# pcb.net
KiCad netlist of a schematic drawn in EAGLE
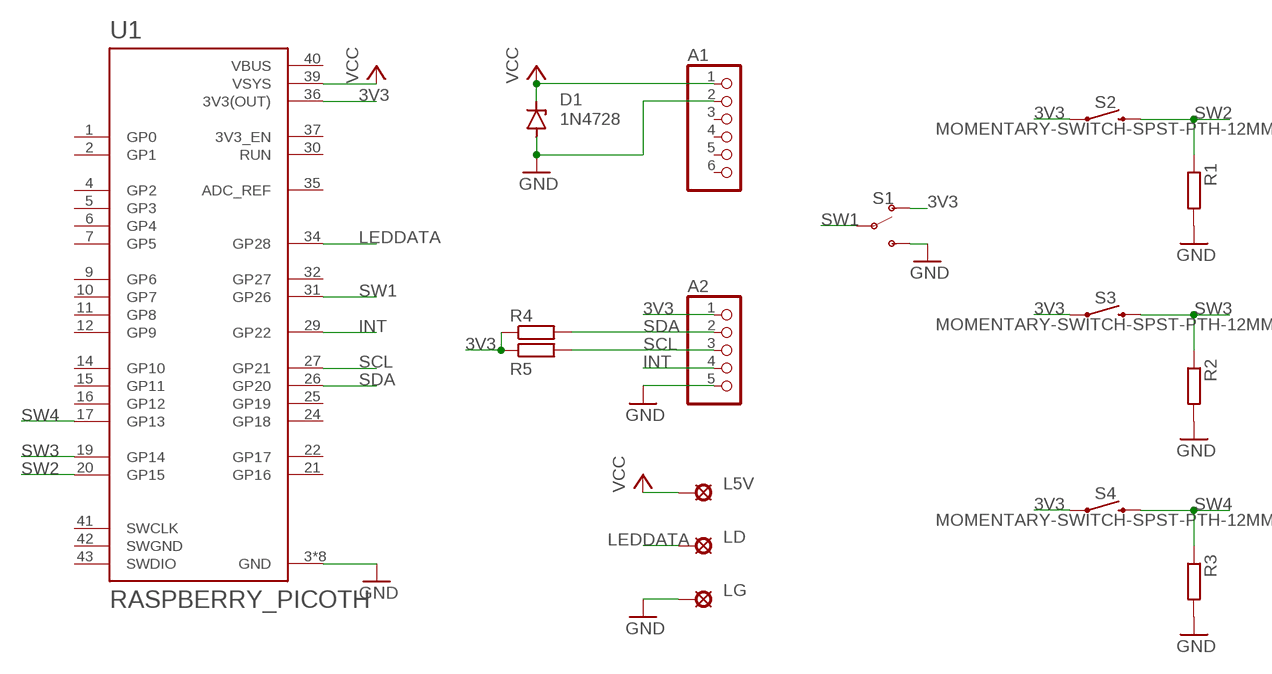
[diagram p0: schematic, sheet 1]

(export (version "E")
  (design (tool "Eeschema 10.0.6"))
  (components
    (comp (ref "A1")
      (value "PINHD-1X6")
      (footprint "eagle-import:1X06")
      (libsource (lib "eagle-import") (part "PINHD-1X6"))
    )
    (comp (ref "A2")
      (value "PINHD-1X5")
      (footprint "eagle-import:1X05")
      (libsource (lib "eagle-import") (part "PINHD-1X5"))
    )
    (comp (ref "D1")
      (value "1N4728")
      (footprint "eagle-import:DO41Z10")
      (libsource (lib "eagle-import") (part "1N4728"))
    )
    (comp (ref "L5V")
      (value "LSP10")
      (footprint "eagle-import:LSP10")
      (libsource (lib "eagle-import") (part "LSP10"))
    )
    (comp (ref "LD")
      (value "LSP10")
      (footprint "eagle-import:LSP10")
      (libsource (lib "eagle-import") (part "LSP10"))
    )
    (comp (ref "LG")
      (value "LSP10")
      (footprint "eagle-import:LSP10")
      (libsource (lib "eagle-import") (part "LSP10"))
    )
    (comp (ref "R1")
      (value "R-EU_0207/7")
      (footprint "eagle-import:0207_7")
      (libsource (lib "eagle-import") (part "R-EU_0207/7"))
    )
    (comp (ref "R2")
      (value "R-EU_0207/7")
      (footprint "eagle-import:0207_7")
      (libsource (lib "eagle-import") (part "R-EU_0207/7"))
    )
    (comp (ref "R3")
      (value "R-EU_0207/7")
      (footprint "eagle-import:0207_7")
      (libsource (lib "eagle-import") (part "R-EU_0207/7"))
    )
    (comp (ref "R4")
      (value "R-EU_0207/7")
      (footprint "eagle-import:0207_7")
      (libsource (lib "eagle-import") (part "R-EU_0207/7"))
    )
    (comp (ref "R5")
      (value "R-EU_0207/7")
      (footprint "eagle-import:0207_7")
      (libsource (lib "eagle-import") (part "R-EU_0207/7"))
    )
    (comp (ref "S1")
      (value "SWITCH-SPDT-PTH-11.6X4.0MM-LOCK")
      (footprint "eagle-import:SWITCH_SPDT_PTH_11.6X4.0MM_LOCK")
      (libsource (lib "eagle-import") (part "SWITCH-SPDT-PTH-11.6X4.0MM-LOCK"))
    )
    (comp (ref "S2")
      (value "MOMENTARY-SWITCH-SPST-PTH-12MM")
      (footprint "eagle-import:TACTILE_SWITCH_PTH_12MM")
      (libsource (lib "eagle-import") (part "MOMENTARY-SWITCH-SPST-PTH-12MM"))
    )
    (comp (ref "S3")
      (value "MOMENTARY-SWITCH-SPST-PTH-12MM")
      (footprint "eagle-import:TACTILE_SWITCH_PTH_12MM")
      (libsource (lib "eagle-import") (part "MOMENTARY-SWITCH-SPST-PTH-12MM"))
    )
    (comp (ref "S4")
      (value "MOMENTARY-SWITCH-SPST-PTH-12MM")
      (footprint "eagle-import:TACTILE_SWITCH_PTH_12MM")
      (libsource (lib "eagle-import") (part "MOMENTARY-SWITCH-SPST-PTH-12MM"))
    )
    (comp (ref "U1")
      (value "RASPBERRY_PICOTH")
      (footprint "eagle-import:PICO-PKG-TH")
      (libsource (lib "eagle-import") (part "RASPBERRY_PICOTH"))
    )
  )
  (nets
    (net (code "1") (name "/3V3") (class "Default")
      (node (ref "A2") (pin "1") (pinfunction "1_1") (pintype "passive"))
      (node (ref "R4") (pin "1") (pinfunction "1_1") (pintype "passive"))
      (node (ref "R5") (pin "1") (pinfunction "1_1") (pintype "passive"))
      (node (ref "S1") (pin "1") (pinfunction "O_1") (pintype "passive"))
      (node (ref "S2") (pin "1") (pinfunction "1_1") (pintype "passive"))
      (node (ref "S3") (pin "1") (pinfunction "1_1") (pintype "passive"))
      (node (ref "S4") (pin "1") (pinfunction "1_1") (pintype "passive"))
      (node (ref "U1") (pin "36") (pinfunction "3V3(OUT)_36") (pintype "power_in"))
    )
    (net (code "2") (name "/INT") (class "Default")
      (node (ref "A2") (pin "4") (pinfunction "4_4") (pintype "passive"))
      (node (ref "U1") (pin "29") (pinfunction "GP22_29") (pintype "bidirectional"))
    )
    (net (code "3") (name "/LEDDATA") (class "Default")
      (node (ref "LD") (pin "MP") (pinfunction "MP_MP") (pintype "passive"))
      (node (ref "U1") (pin "34") (pinfunction "GP28_34") (pintype "bidirectional"))
    )
    (net (code "4") (name "/SCL") (class "Default")
      (node (ref "A2") (pin "3") (pinfunction "3_3") (pintype "passive"))
      (node (ref "R5") (pin "2") (pinfunction "2_2") (pintype "passive"))
      (node (ref "U1") (pin "27") (pinfunction "GP21_27") (pintype "bidirectional"))
    )
    (net (code "5") (name "/SDA") (class "Default")
      (node (ref "A2") (pin "2") (pinfunction "2_2") (pintype "passive"))
      (node (ref "R4") (pin "2") (pinfunction "2_2") (pintype "passive"))
      (node (ref "U1") (pin "26") (pinfunction "GP20_26") (pintype "bidirectional"))
    )
    (net (code "6") (name "/SW1") (class "Default")
      (node (ref "S1") (pin "2") (pinfunction "P_2") (pintype "passive"))
      (node (ref "U1") (pin "31") (pinfunction "GP26_31") (pintype "bidirectional"))
    )
    (net (code "7") (name "/SW2") (class "Default")
      (node (ref "R1") (pin "1") (pinfunction "1_1") (pintype "passive"))
      (node (ref "S2") (pin "3") (pinfunction "2_3") (pintype "passive"))
      (node (ref "U1") (pin "20") (pinfunction "GP15_20") (pintype "bidirectional"))
    )
    (net (code "8") (name "/SW3") (class "Default")
      (node (ref "R2") (pin "1") (pinfunction "1_1") (pintype "passive"))
      (node (ref "S3") (pin "3") (pinfunction "2_3") (pintype "passive"))
      (node (ref "U1") (pin "19") (pinfunction "GP14_19") (pintype "bidirectional"))
    )
    (net (code "9") (name "/SW4") (class "Default")
      (node (ref "R3") (pin "1") (pinfunction "1_1") (pintype "passive"))
      (node (ref "S4") (pin "3") (pinfunction "2_3") (pintype "passive"))
      (node (ref "U1") (pin "17") (pinfunction "GP13_17") (pintype "bidirectional"))
    )
    (net (code "10") (name "/SWGND") (class "Default")
      (node (ref "U1") (pin "42") (pinfunction "SWGND_42") (pintype "power_in"))
    )
    (net (code "11") (name "/VBUS") (class "Default")
      (node (ref "U1") (pin "40") (pinfunction "VBUS_40") (pintype "power_in"))
    )
    (net (code "12") (name "GND") (class "Default")
      (node (ref "A1") (pin "2") (pinfunction "2_2") (pintype "passive"))
      (node (ref "A2") (pin "5") (pinfunction "5_5") (pintype "passive"))
      (node (ref "D1") (pin "A") (pinfunction "A_A") (pintype "passive"))
      (node (ref "LG") (pin "MP") (pinfunction "MP_MP") (pintype "passive"))
      (node (ref "R1") (pin "2") (pinfunction "2_2") (pintype "passive"))
      (node (ref "R2") (pin "2") (pinfunction "2_2") (pintype "passive"))
      (node (ref "R3") (pin "2") (pinfunction "2_2") (pintype "passive"))
      (node (ref "S1") (pin "3") (pinfunction "S_3") (pintype "passive"))
      (node (ref "U1") (pin "13") (pinfunction "GND_13") (pintype "power_in"))
      (node (ref "U1") (pin "18") (pinfunction "GND_18") (pintype "power_in"))
      (node (ref "U1") (pin "23") (pinfunction "GND_23") (pintype "power_in"))
      (node (ref "U1") (pin "28") (pinfunction "GND_28") (pintype "power_in"))
      (node (ref "U1") (pin "3") (pinfunction "GND_3") (pintype "power_in"))
      (node (ref "U1") (pin "33") (pinfunction "GND_33") (pintype "power_in"))
      (node (ref "U1") (pin "38") (pinfunction "GND_38") (pintype "power_in"))
      (node (ref "U1") (pin "8") (pinfunction "GND_8") (pintype "power_in"))
    )
    (net (code "13") (name "VCC") (class "Default")
      (node (ref "A1") (pin "1") (pinfunction "1_1") (pintype "passive"))
      (node (ref "D1") (pin "C") (pinfunction "C_C") (pintype "passive"))
      (node (ref "L5V") (pin "MP") (pinfunction "MP_MP") (pintype "passive"))
      (node (ref "U1") (pin "39") (pinfunction "VSYS_39") (pintype "power_in"))
    )
    (net (code "14") (name "unconnected-(A1-Pad3)") (class "Default")
      (node (ref "A1") (pin "3") (pinfunction "3_3") (pintype "passive"))
    )
    (net (code "15") (name "unconnected-(A1-Pad4)") (class "Default")
      (node (ref "A1") (pin "4") (pinfunction "4_4") (pintype "passive"))
    )
    (net (code "16") (name "unconnected-(A1-Pad5)") (class "Default")
      (node (ref "A1") (pin "5") (pinfunction "5_5") (pintype "passive"))
    )
    (net (code "17") (name "unconnected-(A1-Pad6)") (class "Default")
      (node (ref "A1") (pin "6") (pinfunction "6_6") (pintype "passive"))
    )
    (net (code "18") (name "unconnected-(U1-3V3_EN-Pad37)") (class "Default")
      (node (ref "U1") (pin "37") (pinfunction "3V3_EN_37") (pintype "input"))
    )
    (net (code "19") (name "unconnected-(U1-ADC_REF-Pad35)") (class "Default")
      (node (ref "U1") (pin "35") (pinfunction "ADC_REF_35") (pintype "input"))
    )
    (net (code "20") (name "unconnected-(U1-GP0-Pad1)") (class "Default")
      (node (ref "U1") (pin "1") (pinfunction "GP0_1") (pintype "bidirectional"))
    )
    (net (code "21") (name "unconnected-(U1-GP1-Pad2)") (class "Default")
      (node (ref "U1") (pin "2") (pinfunction "GP1_2") (pintype "bidirectional"))
    )
    (net (code "22") (name "unconnected-(U1-GP2-Pad4)") (class "Default")
      (node (ref "U1") (pin "4") (pinfunction "GP2_4") (pintype "bidirectional"))
    )
    (net (code "23") (name "unconnected-(U1-GP3-Pad5)") (class "Default")
      (node (ref "U1") (pin "5") (pinfunction "GP3_5") (pintype "bidirectional"))
    )
    (net (code "24") (name "unconnected-(U1-GP4-Pad6)") (class "Default")
      (node (ref "U1") (pin "6") (pinfunction "GP4_6") (pintype "bidirectional"))
    )
    (net (code "25") (name "unconnected-(U1-GP5-Pad7)") (class "Default")
      (node (ref "U1") (pin "7") (pinfunction "GP5_7") (pintype "bidirectional"))
    )
    (net (code "26") (name "unconnected-(U1-GP6-Pad9)") (class "Default")
      (node (ref "U1") (pin "9") (pinfunction "GP6_9") (pintype "bidirectional"))
    )
    (net (code "27") (name "unconnected-(U1-GP7-Pad10)") (class "Default")
      (node (ref "U1") (pin "10") (pinfunction "GP7_10") (pintype "bidirectional"))
    )
    (net (code "28") (name "unconnected-(U1-GP8-Pad11)") (class "Default")
      (node (ref "U1") (pin "11") (pinfunction "GP8_11") (pintype "bidirectional"))
    )
    (net (code "29") (name "unconnected-(U1-GP9-Pad12)") (class "Default")
      (node (ref "U1") (pin "12") (pinfunction "GP9_12") (pintype "bidirectional"))
    )
    (net (code "30") (name "unconnected-(U1-GP10-Pad14)") (class "Default")
      (node (ref "U1") (pin "14") (pinfunction "GP10_14") (pintype "bidirectional"))
    )
    (net (code "31") (name "unconnected-(U1-GP11-Pad15)") (class "Default")
      (node (ref "U1") (pin "15") (pinfunction "GP11_15") (pintype "bidirectional"))
    )
    (net (code "32") (name "unconnected-(U1-GP12-Pad16)") (class "Default")
      (node (ref "U1") (pin "16") (pinfunction "GP12_16") (pintype "bidirectional"))
    )
    (net (code "33") (name "unconnected-(U1-GP16-Pad21)") (class "Default")
      (node (ref "U1") (pin "21") (pinfunction "GP16_21") (pintype "bidirectional"))
    )
    (net (code "34") (name "unconnected-(U1-GP17-Pad22)") (class "Default")
      (node (ref "U1") (pin "22") (pinfunction "GP17_22") (pintype "bidirectional"))
    )
    (net (code "35") (name "unconnected-(U1-GP18-Pad24)") (class "Default")
      (node (ref "U1") (pin "24") (pinfunction "GP18_24") (pintype "bidirectional"))
    )
    (net (code "36") (name "unconnected-(U1-GP19-Pad25)") (class "Default")
      (node (ref "U1") (pin "25") (pinfunction "GP19_25") (pintype "bidirectional"))
    )
    (net (code "37") (name "unconnected-(U1-GP27-Pad32)") (class "Default")
      (node (ref "U1") (pin "32") (pinfunction "GP27_32") (pintype "bidirectional"))
    )
    (net (code "38") (name "unconnected-(U1-RUN-Pad30)") (class "Default")
      (node (ref "U1") (pin "30") (pinfunction "RUN_30") (pintype "input"))
    )
    (net (code "39") (name "unconnected-(U1-SWCLK-Pad41)") (class "Default")
      (node (ref "U1") (pin "41") (pinfunction "SWCLK_41") (pintype "input"))
    )
    (net (code "40") (name "unconnected-(U1-SWDIO-Pad43)") (class "Default")
      (node (ref "U1") (pin "43") (pinfunction "SWDIO_43") (pintype "bidirectional"))
    )
  )
)
